# Receiver.net
KiCad netlist of a schematic drawn in Altium Designer
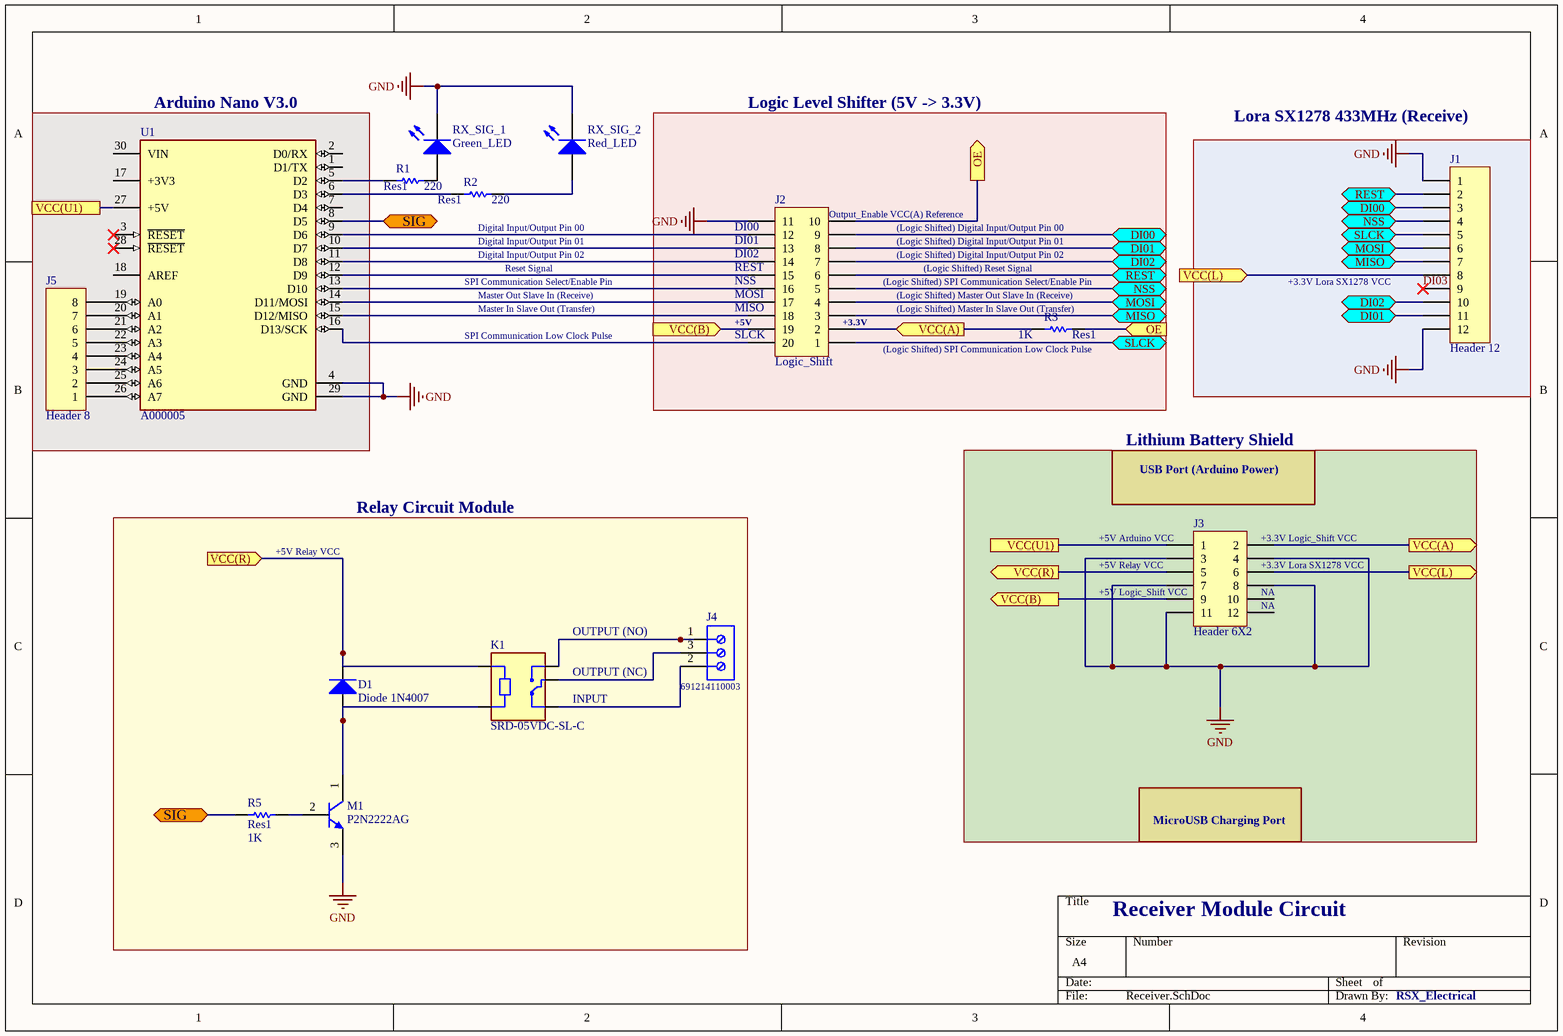
[diagram p0: Receiver.SchDoc]

(export (version "E")
  (design (tool "Eeschema 10.0.6"))
  (components
    (comp (ref "D1")
      (value "Diode 1N4007")
      (footprint "DO-41")
      (description "1 Amp General Purpose Rectifier")
      (fields (field (name "PUBLISHER") "Altium Limited"))
      (libsource (lib "Miscellaneous Devices") (part "Diode 1N4007"))
    )
    (comp (ref "J1")
      (value "Header 12")
      (footprint "LORA Sx1278")
      (description "Header, 12-Pin")
      (fields (field (name "PUBLISHER") "Altium Limited"))
      (libsource (lib "Miscellaneous Connectors") (part "Header 12"))
    )
    (comp (ref "J2")
      (value "Logic_Shift")
      (footprint "DIP2SSOP20")
      (description "Header, 10-Pin, Dual row")
      (fields (field (name "PUBLISHER") "Altium Limited"))
      (libsource (lib "Miscellaneous Connectors") (part "Header 10X2"))
    )
    (comp (ref "J3")
      (value "Header 6X2")
      (footprint "3.3V/5V Battery Shield")
      (description "Header, 6-Pin, Dual row")
      (fields (field (name "PUBLISHER") "Altium Limited"))
      (libsource (lib "Miscellaneous Connectors") (part "Header 6X2"))
    )
    (comp (ref "J4")
      (value "691214110003")
      (footprint "691214110003")
      (description "Serie 2141 - 3.50 mm Horizontal Entry Modular with Rising Cage Clamp WR-TBL, 3 pin")
      (fields (field (name "MANUFACTURER") "Wurth Elektronik") (field (name "PUBLISHER") "WurthElektronik"))
      (libsource (lib "Altium Content Vault") (part "WE-CN-1P-F-TB3"))
    )
    (comp (ref "J5")
      (value "Header 8")
      (footprint "HDR1X8")
      (description "Header, 8-Pin")
      (fields (field (name "PUBLISHER") "Altium Limited"))
      (libsource (lib "Miscellaneous Connectors") (part "Header 8"))
    )
    (comp (ref "K1")
      (value "SRD-05VDC-SL-C")
      (footprint "RELAY_SRD-05VDC-SL-C")
      (fields (field (name "MF") "Songle Relay"))
      (libsource (lib "SRD-05VDC-SL-C") (part "SRD-05VDC-SL-C"))
    )
    (comp (ref "M1")
      (value "P2N2222AG")
      (footprint "ONSC-TO-92-3-29-11")
      (description "Amplifier Transistor, NPN Silicon, 3-Pin TO-92, Pb-Free, Bulk Box")
      (fields (field (name "MANUFACTURER") "On Semiconductor"))
      (libsource (lib "Altium Content Vault") (part "ONSC-NPN-C1B2E3-3"))
    )
    (comp (ref "R1")
      (value "Res1")
      (footprint "AXIAL-0.3")
      (description "Resistor")
      (fields (field (name "ALTIUM_VALUE") "220") (field (name "PUBLISHER") "Altium Limited"))
      (libsource (lib "Miscellaneous Devices") (part "Res1"))
    )
    (comp (ref "R2")
      (value "Res1")
      (footprint "AXIAL-0.3")
      (description "Resistor")
      (fields (field (name "ALTIUM_VALUE") "220") (field (name "PUBLISHER") "Altium Limited"))
      (libsource (lib "Miscellaneous Devices") (part "Res1"))
    )
    (comp (ref "R3")
      (value "Res1")
      (footprint "AXIAL-0.3")
      (description "Resistor")
      (fields (field (name "ALTIUM_VALUE") "1K") (field (name "PUBLISHER") "Altium Limited"))
      (libsource (lib "Miscellaneous Devices") (part "Res1"))
    )
    (comp (ref "R5")
      (value "Res1")
      (footprint "AXIAL-0.3")
      (description "Resistor")
      (fields (field (name "ALTIUM_VALUE") "1K") (field (name "PUBLISHER") "Altium Limited"))
      (libsource (lib "Miscellaneous Devices") (part "Res1"))
    )
    (comp (ref "RX_SIG_1")
      (value "Green_LED")
      (footprint "LED-0")
      (description "Typical INFRARED GaAs LED")
      (fields (field (name "PUBLISHER") "Altium Limited"))
      (libsource (lib "Miscellaneous Devices") (part "LED0"))
    )
    (comp (ref "RX_SIG_2")
      (value "Red_LED")
      (footprint "LED-0")
      (description "Typical INFRARED GaAs LED")
      (fields (field (name "PUBLISHER") "Altium Limited"))
      (libsource (lib "Miscellaneous Devices") (part "LED0"))
    )
    (comp (ref "U1")
      (value "A000005")
      (footprint "FP-A000005-MFG")
      (description "ARDUINO NANO ATMEGA328 EVAL BRD")
      (libsource (lib "Altium Content Vault") (part "d190c066e99afd1c6882cf92e11b2cc"))
    )
  )
  (nets
    (net (code "1") (name "/DI00") (class "Default")
      (node (ref "J1") (pin "3") (pinfunction "3_3") (pintype "passive"))
      (node (ref "J2") (pin "9") (pinfunction "9_9") (pintype "passive"))
    )
    (net (code "2") (name "/DI01") (class "Default")
      (node (ref "J1") (pin "11") (pinfunction "11_11") (pintype "passive"))
      (node (ref "J2") (pin "8") (pinfunction "8_8") (pintype "passive"))
    )
    (net (code "3") (name "/DI02") (class "Default")
      (node (ref "J1") (pin "10") (pinfunction "10_10") (pintype "passive"))
      (node (ref "J2") (pin "7") (pinfunction "7_7") (pintype "passive"))
    )
    (net (code "4") (name "/DI03") (class "Default")
      (node (ref "J1") (pin "9") (pinfunction "9_9") (pintype "passive+no_connect"))
    )
    (net (code "5") (name "/MISO") (class "Default")
      (node (ref "J1") (pin "7") (pinfunction "7_7") (pintype "passive"))
      (node (ref "J2") (pin "3") (pinfunction "3_3") (pintype "passive"))
    )
    (net (code "6") (name "/MOSI") (class "Default")
      (node (ref "J1") (pin "6") (pinfunction "6_6") (pintype "passive"))
      (node (ref "J2") (pin "4") (pinfunction "4_4") (pintype "passive"))
    )
    (net (code "7") (name "/NSS") (class "Default")
      (node (ref "J1") (pin "4") (pinfunction "4_4") (pintype "passive"))
      (node (ref "J2") (pin "5") (pinfunction "5_5") (pintype "passive"))
    )
    (net (code "8") (name "/OE") (class "Default")
      (node (ref "J2") (pin "10") (pinfunction "10_10") (pintype "passive"))
      (node (ref "R3") (pin "1") (pinfunction "1_1") (pintype "passive"))
    )
    (net (code "9") (name "/REST") (class "Default")
      (node (ref "J1") (pin "2") (pinfunction "2_2") (pintype "passive"))
      (node (ref "J2") (pin "6") (pinfunction "6_6") (pintype "passive"))
    )
    (net (code "10") (name "/SIG") (class "Default")
      (node (ref "R5") (pin "1") (pinfunction "1_1") (pintype "passive"))
      (node (ref "U1") (pin "8") (pinfunction "D5_8") (pintype "bidirectional"))
    )
    (net (code "11") (name "/SLCK") (class "Default")
      (node (ref "J1") (pin "5") (pinfunction "5_5") (pintype "passive"))
      (node (ref "J2") (pin "1") (pinfunction "1_1") (pintype "passive"))
    )
    (net (code "12") (name "/VCC(A)") (class "Default")
      (node (ref "J2") (pin "2") (pinfunction "2_2") (pintype "passive"))
      (node (ref "J3") (pin "2") (pinfunction "2_2") (pintype "passive"))
      (node (ref "R3") (pin "2") (pinfunction "2_2") (pintype "passive"))
    )
    (net (code "13") (name "/VCC(B)") (class "Default")
      (node (ref "J2") (pin "19") (pinfunction "19_19") (pintype "passive"))
      (node (ref "J3") (pin "9") (pinfunction "9_9") (pintype "passive"))
    )
    (net (code "14") (name "/VCC(L)") (class "Default")
      (node (ref "J1") (pin "8") (pinfunction "8_8") (pintype "passive"))
      (node (ref "J3") (pin "6") (pinfunction "6_6") (pintype "passive"))
    )
    (net (code "15") (name "/VCC(R)") (class "Default")
      (node (ref "D1") (pin "2") (pinfunction "K_2") (pintype "passive"))
      (node (ref "J3") (pin "5") (pinfunction "5_5") (pintype "passive"))
      (node (ref "K1") (pin "A1") (pinfunction "A1_A1") (pintype "passive"))
    )
    (net (code "16") (name "/VCC(U1)") (class "Default")
      (node (ref "J3") (pin "1") (pinfunction "1_1") (pintype "passive"))
      (node (ref "U1") (pin "27") (pinfunction "+5V_27") (pintype "power_in"))
    )
    (net (code "17") (name "GND") (class "Default")
      (node (ref "J1") (pin "1") (pinfunction "1_1") (pintype "passive"))
      (node (ref "J1") (pin "12") (pinfunction "12_12") (pintype "passive"))
      (node (ref "J2") (pin "11") (pinfunction "11_11") (pintype "passive"))
      (node (ref "J3") (pin "11") (pinfunction "11_11") (pintype "passive"))
      (node (ref "J3") (pin "3") (pinfunction "3_3") (pintype "passive"))
      (node (ref "J3") (pin "4") (pinfunction "4_4") (pintype "passive"))
      (node (ref "J3") (pin "7") (pinfunction "7_7") (pintype "passive"))
      (node (ref "J3") (pin "8") (pinfunction "8_8") (pintype "passive"))
      (node (ref "M1") (pin "3") (pinfunction "E_3") (pintype "passive"))
      (node (ref "RX_SIG_1") (pin "2") (pinfunction "K_2") (pintype "passive"))
      (node (ref "RX_SIG_2") (pin "2") (pinfunction "K_2") (pintype "passive"))
      (node (ref "U1") (pin "29") (pinfunction "GND_29") (pintype "power_in"))
      (node (ref "U1") (pin "4") (pinfunction "GND_4") (pintype "power_in"))
    )
    (net (code "18") (name "Net-(D1-A)") (class "Default")
      (node (ref "D1") (pin "1") (pinfunction "A_1") (pintype "passive"))
      (node (ref "K1") (pin "A2") (pinfunction "A2_A2") (pintype "passive"))
      (node (ref "M1") (pin "1") (pinfunction "C_1") (pintype "passive"))
    )
    (net (code "19") (name "Net-(J4-2)") (class "Default")
      (node (ref "J4") (pin "3") (pinfunction "2_3") (pintype "passive"))
      (node (ref "K1") (pin "COM") (pinfunction "COM_COM") (pintype "passive"))
    )
    (net (code "20") (name "Net-(J4-3)") (class "Default")
      (node (ref "J4") (pin "2") (pinfunction "3_2") (pintype "passive"))
      (node (ref "K1") (pin "NC") (pinfunction "NC_NC") (pintype "passive"))
    )
    (net (code "21") (name "Net-(J4-Pad1)") (class "Default")
      (node (ref "J4") (pin "1") (pinfunction "1_1") (pintype "passive"))
      (node (ref "K1") (pin "NO") (pinfunction "NO_NO") (pintype "passive"))
    )
    (net (code "22") (name "Net-(M1-B)") (class "Default")
      (node (ref "M1") (pin "2") (pinfunction "B_2") (pintype "passive"))
      (node (ref "R5") (pin "2") (pinfunction "2_2") (pintype "passive"))
    )
    (net (code "23") (name "Net-(RX_SIG_1-A)") (class "Default")
      (node (ref "R1") (pin "1") (pinfunction "1_1") (pintype "passive"))
      (node (ref "RX_SIG_1") (pin "1") (pinfunction "A_1") (pintype "passive"))
    )
    (net (code "24") (name "Net-(RX_SIG_2-A)") (class "Default")
      (node (ref "R2") (pin "1") (pinfunction "1_1") (pintype "passive"))
      (node (ref "RX_SIG_2") (pin "1") (pinfunction "A_1") (pintype "passive"))
    )
    (net (code "25") (name "Net-(U1-A0)") (class "Default")
      (node (ref "J5") (pin "8") (pinfunction "8_8") (pintype "passive"))
      (node (ref "U1") (pin "19") (pinfunction "A0_19") (pintype "bidirectional"))
    )
    (net (code "26") (name "Net-(U1-A1)") (class "Default")
      (node (ref "J5") (pin "7") (pinfunction "7_7") (pintype "passive"))
      (node (ref "U1") (pin "20") (pinfunction "A1_20") (pintype "bidirectional"))
    )
    (net (code "27") (name "Net-(U1-A2)") (class "Default")
      (node (ref "J5") (pin "6") (pinfunction "6_6") (pintype "passive"))
      (node (ref "U1") (pin "21") (pinfunction "A2_21") (pintype "bidirectional"))
    )
    (net (code "28") (name "Net-(U1-A3)") (class "Default")
      (node (ref "J5") (pin "5") (pinfunction "5_5") (pintype "passive"))
      (node (ref "U1") (pin "22") (pinfunction "A3_22") (pintype "bidirectional"))
    )
    (net (code "29") (name "Net-(U1-A4)") (class "Default")
      (node (ref "J5") (pin "4") (pinfunction "4_4") (pintype "passive"))
      (node (ref "U1") (pin "23") (pinfunction "A4_23") (pintype "bidirectional"))
    )
    (net (code "30") (name "Net-(U1-A5)") (class "Default")
      (node (ref "J5") (pin "3") (pinfunction "3_3") (pintype "passive"))
      (node (ref "U1") (pin "24") (pinfunction "A5_24") (pintype "bidirectional"))
    )
    (net (code "31") (name "Net-(U1-A6)") (class "Default")
      (node (ref "J5") (pin "2") (pinfunction "2_2") (pintype "passive"))
      (node (ref "U1") (pin "25") (pinfunction "A6_25") (pintype "bidirectional"))
    )
    (net (code "32") (name "Net-(U1-A7)") (class "Default")
      (node (ref "J5") (pin "1") (pinfunction "1_1") (pintype "passive"))
      (node (ref "U1") (pin "26") (pinfunction "A7_26") (pintype "bidirectional"))
    )
    (net (code "33") (name "Net-(U1-D2)") (class "Default")
      (node (ref "R1") (pin "2") (pinfunction "2_2") (pintype "passive"))
      (node (ref "U1") (pin "5") (pinfunction "D2_5") (pintype "bidirectional"))
    )
    (net (code "34") (name "Net-(U1-D3)") (class "Default")
      (node (ref "R2") (pin "2") (pinfunction "2_2") (pintype "passive"))
      (node (ref "U1") (pin "6") (pinfunction "D3_6") (pintype "bidirectional"))
    )
    (net (code "35") (name "Net-(U1-D6)") (class "Default")
      (node (ref "J2") (pin "12") (pinfunction "12_12") (pintype "passive"))
      (node (ref "U1") (pin "9") (pinfunction "D6_9") (pintype "bidirectional"))
    )
    (net (code "36") (name "Net-(U1-D7)") (class "Default")
      (node (ref "J2") (pin "13") (pinfunction "13_13") (pintype "passive"))
      (node (ref "U1") (pin "10") (pinfunction "D7_10") (pintype "bidirectional"))
    )
    (net (code "37") (name "Net-(U1-D8)") (class "Default")
      (node (ref "J2") (pin "14") (pinfunction "14_14") (pintype "passive"))
      (node (ref "U1") (pin "11") (pinfunction "D8_11") (pintype "bidirectional"))
    )
    (net (code "38") (name "Net-(U1-D9)") (class "Default")
      (node (ref "J2") (pin "15") (pinfunction "15_15") (pintype "passive"))
      (node (ref "U1") (pin "12") (pinfunction "D9_12") (pintype "bidirectional"))
    )
    (net (code "39") (name "Net-(U1-D10)") (class "Default")
      (node (ref "J2") (pin "16") (pinfunction "16_16") (pintype "passive"))
      (node (ref "U1") (pin "13") (pinfunction "D10_13") (pintype "bidirectional"))
    )
    (net (code "40") (name "Net-(U1-D11{slash}MOSI)") (class "Default")
      (node (ref "J2") (pin "17") (pinfunction "17_17") (pintype "passive"))
      (node (ref "U1") (pin "14") (pinfunction "D11/MOSI_14") (pintype "bidirectional"))
    )
    (net (code "41") (name "Net-(U1-D12{slash}MISO)") (class "Default")
      (node (ref "J2") (pin "18") (pinfunction "18_18") (pintype "passive"))
      (node (ref "U1") (pin "15") (pinfunction "D12/MISO_15") (pintype "bidirectional"))
    )
    (net (code "42") (name "Net-(U1-D13{slash}SCK)") (class "Default")
      (node (ref "J2") (pin "20") (pinfunction "20_20") (pintype "passive"))
      (node (ref "U1") (pin "16") (pinfunction "D13/SCK_16") (pintype "bidirectional"))
    )
    (net (code "43") (name "unconnected-(J3-Pad10)") (class "Default")
      (node (ref "J3") (pin "10") (pinfunction "10_10") (pintype "passive"))
    )
    (net (code "44") (name "unconnected-(J3-Pad12)") (class "Default")
      (node (ref "J3") (pin "12") (pinfunction "12_12") (pintype "passive"))
    )
    (net (code "45") (name "unconnected-(U1-+3V3-Pad17)") (class "Default")
      (node (ref "U1") (pin "17") (pinfunction "+3V3_17") (pintype "power_in"))
    )
    (net (code "46") (name "unconnected-(U1-AREF-Pad18)") (class "Default")
      (node (ref "U1") (pin "18") (pinfunction "AREF_18") (pintype "passive"))
    )
    (net (code "47") (name "unconnected-(U1-D0{slash}RX-Pad2)") (class "Default")
      (node (ref "U1") (pin "2") (pinfunction "D0/RX_2") (pintype "bidirectional"))
    )
    (net (code "48") (name "unconnected-(U1-D1{slash}TX-Pad1)") (class "Default")
      (node (ref "U1") (pin "1") (pinfunction "D1/TX_1") (pintype "bidirectional"))
    )
    (net (code "49") (name "unconnected-(U1-D4-Pad7)") (class "Default")
      (node (ref "U1") (pin "7") (pinfunction "D4_7") (pintype "bidirectional"))
    )
    (net (code "50") (name "unconnected-(U1-VIN-Pad30)") (class "Default")
      (node (ref "U1") (pin "30") (pinfunction "VIN_30") (pintype "power_in"))
    )
    (net (code "51") (name "unconnected-(U1-~{RESET}-Pad3)") (class "Default")
      (node (ref "U1") (pin "3") (pinfunction "~{RESET}_3") (pintype "input+no_connect"))
    )
    (net (code "52") (name "unconnected-(U1-~{RESET}-Pad28)") (class "Default")
      (node (ref "U1") (pin "28") (pinfunction "~{RESET}_28") (pintype "input+no_connect"))
    )
  )
)
